# 01_MCU.net
KiCad netlist of a schematic drawn in Altium Designer
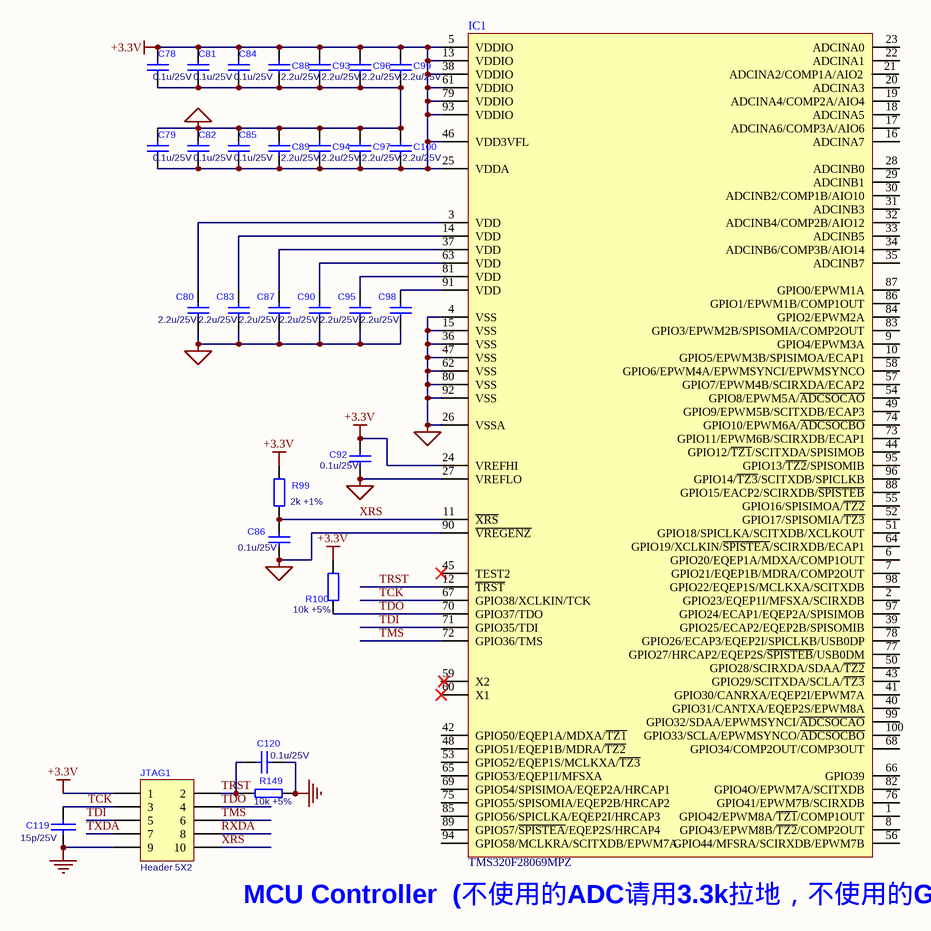
[diagram p0: 01_MCU.SchDoc]

(export (version "E")
  (design (tool "Eeschema 10.0.6"))
  (components
    (comp (ref "C78")
      (value "0.1u/25V")
      (footprint "C0603")
      (description "Capacitor")
      (fields (field (name "PUBLISHER") "Altium Limited"))
      (libsource (lib "*") (part "Cap"))
    )
    (comp (ref "C79")
      (value "0.1u/25V")
      (footprint "R0603")
      (description "Capacitor")
      (fields (field (name "PUBLISHER") "Altium Limited"))
      (libsource (lib "*") (part "Cap"))
    )
    (comp (ref "C80")
      (value "2.2u/25V")
      (footprint "R0603")
      (description "Capacitor")
      (fields (field (name "PUBLISHER") "Altium Limited"))
      (libsource (lib "*") (part "Cap"))
    )
    (comp (ref "C81")
      (value "0.1u/25V")
      (footprint "C0603")
      (description "Capacitor")
      (fields (field (name "PUBLISHER") "Altium Limited"))
      (libsource (lib "*") (part "Cap"))
    )
    (comp (ref "C82")
      (value "0.1u/25V")
      (footprint "R0603")
      (description "Capacitor")
      (fields (field (name "PUBLISHER") "Altium Limited"))
      (libsource (lib "*") (part "Cap"))
    )
    (comp (ref "C83")
      (value "2.2u/25V")
      (footprint "R0603")
      (description "Capacitor")
      (fields (field (name "PUBLISHER") "Altium Limited"))
      (libsource (lib "*") (part "Cap"))
    )
    (comp (ref "C84")
      (value "0.1u/25V")
      (footprint "R0603")
      (description "Capacitor")
      (fields (field (name "PUBLISHER") "Altium Limited"))
      (libsource (lib "*") (part "Cap"))
    )
    (comp (ref "C85")
      (value "0.1u/25V")
      (footprint "R0603")
      (description "Capacitor")
      (fields (field (name "PUBLISHER") "Altium Limited"))
      (libsource (lib "*") (part "Cap"))
    )
    (comp (ref "C86")
      (value "0.1u/25V")
      (footprint "R0603")
      (description "Capacitor")
      (fields (field (name "PUBLISHER") "Altium Limited"))
      (libsource (lib "*") (part "Cap"))
    )
    (comp (ref "C87")
      (value "2.2u/25V")
      (footprint "R0603")
      (description "Capacitor")
      (fields (field (name "PUBLISHER") "Altium Limited"))
      (libsource (lib "*") (part "Cap"))
    )
    (comp (ref "C88")
      (value "2.2u/25V")
      (footprint "R0603")
      (description "Capacitor")
      (fields (field (name "PUBLISHER") "Altium Limited"))
      (libsource (lib "*") (part "Cap"))
    )
    (comp (ref "C89")
      (value "2.2u/25V")
      (footprint "R0603")
      (description "Capacitor")
      (fields (field (name "PUBLISHER") "Altium Limited"))
      (libsource (lib "*") (part "Cap"))
    )
    (comp (ref "C90")
      (value "2.2u/25V")
      (footprint "R0603")
      (description "Capacitor")
      (fields (field (name "PUBLISHER") "Altium Limited"))
      (libsource (lib "*") (part "Cap"))
    )
    (comp (ref "C92")
      (value "0.1u/25V")
      (footprint "R0603")
      (description "Capacitor")
      (fields (field (name "PUBLISHER") "Altium Limited"))
      (libsource (lib "*") (part "Cap"))
    )
    (comp (ref "C93")
      (value "2.2u/25V")
      (footprint "R0603")
      (description "Capacitor")
      (fields (field (name "PUBLISHER") "Altium Limited"))
      (libsource (lib "*") (part "Cap"))
    )
    (comp (ref "C94")
      (value "2.2u/25V")
      (footprint "R0603")
      (description "Capacitor")
      (fields (field (name "PUBLISHER") "Altium Limited"))
      (libsource (lib "*") (part "Cap"))
    )
    (comp (ref "C95")
      (value "2.2u/25V")
      (footprint "R0603")
      (description "Capacitor")
      (fields (field (name "PUBLISHER") "Altium Limited"))
      (libsource (lib "*") (part "Cap"))
    )
    (comp (ref "C96")
      (value "2.2u/25V")
      (footprint "R0603")
      (description "Capacitor")
      (fields (field (name "PUBLISHER") "Altium Limited"))
      (libsource (lib "*") (part "Cap"))
    )
    (comp (ref "C97")
      (value "2.2u/25V")
      (footprint "R0603")
      (description "Capacitor")
      (fields (field (name "PUBLISHER") "Altium Limited"))
      (libsource (lib "*") (part "Cap"))
    )
    (comp (ref "C98")
      (value "2.2u/25V")
      (footprint "R0603")
      (description "Capacitor")
      (fields (field (name "PUBLISHER") "Altium Limited"))
      (libsource (lib "*") (part "Cap"))
    )
    (comp (ref "C99")
      (value "2.2u/25V")
      (footprint "R0603")
      (description "Capacitor")
      (fields (field (name "PUBLISHER") "Altium Limited"))
      (libsource (lib "*") (part "Cap"))
    )
    (comp (ref "C100")
      (value "2.2u/25V")
      (footprint "R0603")
      (description "Capacitor")
      (fields (field (name "PUBLISHER") "Altium Limited"))
      (libsource (lib "*") (part "Cap"))
    )
    (comp (ref "C119")
      (value "15p/25V")
      (footprint "R0603")
      (description "Capacitor")
      (libsource (lib "*") (part "CAP"))
    )
    (comp (ref "C120")
      (value "0.1u/25V")
      (footprint "R0603")
      (description "Capacitor")
      (fields (field (name "PUBLISHER") "Altium Limited"))
      (libsource (lib "*") (part "Cap"))
    )
    (comp (ref "IC1")
      (value "TMS320F28069MPZ")
      (footprint "RX62T")
      (description "TI MCU_TMS320F28069")
      (libsource (lib "*") (part "IC-TMS320F28062"))
    )
    (comp (ref "JTAG1")
      (value "Header 5X2")
      (footprint "PZ-2*5-M-SI")
      (description "Header, 5-Pin, Dual row")
      (fields (field (name "MANUFACTURER") "Generic Components") (field (name "PUBLISHER") "Altium Limited"))
      (libsource (lib "*") (part "Header 5X2"))
    )
    (comp (ref "R99")
      (value "2k +1%")
      (footprint "R0603")
      (description "Resistor")
      (fields (field (name "PUBLISHER") "Altium Limited"))
      (libsource (lib "*") (part "Res2"))
    )
    (comp (ref "R100")
      (value "10k +5%")
      (footprint "R0603")
      (description "Resistor")
      (fields (field (name "PUBLISHER") "Altium Limited"))
      (libsource (lib "*") (part "Res2"))
    )
    (comp (ref "R149") (value "10k +5%") (footprint "R0603") (libsource (lib "*") (part "RES/0603")))
  )
  (nets
    (net (code "1") (name "+3.3V") (class "Default")
      (node (ref "C100") (pin "2") (pinfunction "2_2") (pintype "passive"))
      (node (ref "C78") (pin "1") (pinfunction "1_1") (pintype "passive"))
      (node (ref "C79") (pin "2") (pinfunction "2_2") (pintype "passive"))
      (node (ref "C81") (pin "1") (pinfunction "1_1") (pintype "passive"))
      (node (ref "C82") (pin "2") (pinfunction "2_2") (pintype "passive"))
      (node (ref "C84") (pin "1") (pinfunction "1_1") (pintype "passive"))
      (node (ref "C85") (pin "2") (pinfunction "2_2") (pintype "passive"))
      (node (ref "C88") (pin "1") (pinfunction "1_1") (pintype "passive"))
      (node (ref "C89") (pin "2") (pinfunction "2_2") (pintype "passive"))
      (node (ref "C92") (pin "1") (pinfunction "1_1") (pintype "passive"))
      (node (ref "C93") (pin "1") (pinfunction "1_1") (pintype "passive"))
      (node (ref "C94") (pin "2") (pinfunction "2_2") (pintype "passive"))
      (node (ref "C96") (pin "1") (pinfunction "1_1") (pintype "passive"))
      (node (ref "C97") (pin "2") (pinfunction "2_2") (pintype "passive"))
      (node (ref "C99") (pin "1") (pinfunction "1_1") (pintype "passive"))
      (node (ref "IC1") (pin "13") (pinfunction "VDDIO_13") (pintype "passive"))
      (node (ref "IC1") (pin "24") (pinfunction "VREFHI_24") (pintype "passive"))
      (node (ref "IC1") (pin "25") (pinfunction "VDDA_25") (pintype "passive"))
      (node (ref "IC1") (pin "38") (pinfunction "VDDIO_38") (pintype "passive"))
      (node (ref "IC1") (pin "46") (pinfunction "VDD3VFL_46") (pintype "passive"))
      (node (ref "IC1") (pin "5") (pinfunction "VDDIO_5") (pintype "passive"))
      (node (ref "IC1") (pin "61") (pinfunction "VDDIO_61") (pintype "passive"))
      (node (ref "IC1") (pin "79") (pinfunction "VDDIO_79") (pintype "passive"))
      (node (ref "IC1") (pin "93") (pinfunction "VDDIO_93") (pintype "passive"))
      (node (ref "JTAG1") (pin "1") (pinfunction "1_1") (pintype "passive"))
      (node (ref "R100") (pin "2") (pinfunction "2_2") (pintype "passive"))
      (node (ref "R99") (pin "2") (pinfunction "2_2") (pintype "passive"))
    )
    (net (code "2") (name "/RXDA") (class "Default")
      (node (ref "JTAG1") (pin "8") (pinfunction "8_8") (pintype "passive"))
    )
    (net (code "3") (name "/TCK") (class "Default")
      (node (ref "C119") (pin "1") (pinfunction "1_1") (pintype "passive"))
      (node (ref "IC1") (pin "67") (pinfunction "GPIO38/XCLKIN/TCK_67") (pintype "passive"))
      (node (ref "JTAG1") (pin "3") (pinfunction "3_3") (pintype "passive"))
    )
    (net (code "4") (name "/TDI") (class "Default")
      (node (ref "IC1") (pin "71") (pinfunction "GPIO35/TDI_71") (pintype "passive"))
      (node (ref "JTAG1") (pin "5") (pinfunction "5_5") (pintype "passive"))
    )
    (net (code "5") (name "/TDO") (class "Default")
      (node (ref "IC1") (pin "70") (pinfunction "GPIO37/TDO_70") (pintype "passive"))
      (node (ref "JTAG1") (pin "4") (pinfunction "4_4") (pintype "passive"))
      (node (ref "R100") (pin "1") (pinfunction "1_1") (pintype "passive"))
    )
    (net (code "6") (name "/TMS") (class "Default")
      (node (ref "IC1") (pin "72") (pinfunction "GPIO36/TMS_72") (pintype "passive"))
      (node (ref "JTAG1") (pin "6") (pinfunction "6_6") (pintype "passive"))
    )
    (net (code "7") (name "/TRST") (class "Default")
      (node (ref "C120") (pin "2") (pinfunction "2_2") (pintype "passive"))
      (node (ref "IC1") (pin "12") (pinfunction "~{TRST}_12") (pintype "passive"))
      (node (ref "JTAG1") (pin "2") (pinfunction "2_2") (pintype "passive"))
      (node (ref "R149") (pin "1") (pinfunction "1_1") (pintype "passive"))
    )
    (net (code "8") (name "/TXDA") (class "Default")
      (node (ref "JTAG1") (pin "7") (pinfunction "7_7") (pintype "passive"))
    )
    (net (code "9") (name "/XRS") (class "Default")
      (node (ref "C86") (pin "1") (pinfunction "1_1") (pintype "passive"))
      (node (ref "IC1") (pin "11") (pinfunction "~{XRS}_11") (pintype "passive"))
      (node (ref "JTAG1") (pin "10") (pinfunction "10_10") (pintype "passive"))
      (node (ref "R99") (pin "1") (pinfunction "1_1") (pintype "passive"))
    )
    (net (code "10") (name "GND") (class "Default")
      (node (ref "C100") (pin "1") (pinfunction "1_1") (pintype "passive"))
      (node (ref "C119") (pin "2") (pinfunction "2_2") (pintype "passive"))
      (node (ref "C120") (pin "1") (pinfunction "1_1") (pintype "passive"))
      (node (ref "C78") (pin "2") (pinfunction "2_2") (pintype "passive"))
      (node (ref "C79") (pin "1") (pinfunction "1_1") (pintype "passive"))
      (node (ref "C80") (pin "2") (pinfunction "2_2") (pintype "passive"))
      (node (ref "C81") (pin "2") (pinfunction "2_2") (pintype "passive"))
      (node (ref "C82") (pin "1") (pinfunction "1_1") (pintype "passive"))
      (node (ref "C83") (pin "2") (pinfunction "2_2") (pintype "passive"))
      (node (ref "C84") (pin "2") (pinfunction "2_2") (pintype "passive"))
      (node (ref "C85") (pin "1") (pinfunction "1_1") (pintype "passive"))
      (node (ref "C86") (pin "2") (pinfunction "2_2") (pintype "passive"))
      (node (ref "C87") (pin "2") (pinfunction "2_2") (pintype "passive"))
      (node (ref "C88") (pin "2") (pinfunction "2_2") (pintype "passive"))
      (node (ref "C89") (pin "1") (pinfunction "1_1") (pintype "passive"))
      (node (ref "C90") (pin "2") (pinfunction "2_2") (pintype "passive"))
      (node (ref "C92") (pin "2") (pinfunction "2_2") (pintype "passive"))
      (node (ref "C93") (pin "2") (pinfunction "2_2") (pintype "passive"))
      (node (ref "C94") (pin "1") (pinfunction "1_1") (pintype "passive"))
      (node (ref "C95") (pin "2") (pinfunction "2_2") (pintype "passive"))
      (node (ref "C96") (pin "2") (pinfunction "2_2") (pintype "passive"))
      (node (ref "C97") (pin "1") (pinfunction "1_1") (pintype "passive"))
      (node (ref "C98") (pin "2") (pinfunction "2_2") (pintype "passive"))
      (node (ref "C99") (pin "2") (pinfunction "2_2") (pintype "passive"))
      (node (ref "IC1") (pin "15") (pinfunction "VSS_15") (pintype "passive"))
      (node (ref "IC1") (pin "26") (pinfunction "VSSA_26") (pintype "passive"))
      (node (ref "IC1") (pin "27") (pinfunction "VREFLO_27") (pintype "passive"))
      (node (ref "IC1") (pin "36") (pinfunction "VSS_36") (pintype "passive"))
      (node (ref "IC1") (pin "4") (pinfunction "VSS_4") (pintype "passive"))
      (node (ref "IC1") (pin "47") (pinfunction "VSS_47") (pintype "passive"))
      (node (ref "IC1") (pin "62") (pinfunction "VSS_62") (pintype "passive"))
      (node (ref "IC1") (pin "80") (pinfunction "VSS_80") (pintype "passive"))
      (node (ref "IC1") (pin "90") (pinfunction "~{VREGENZ}_90") (pintype "passive"))
      (node (ref "IC1") (pin "92") (pinfunction "VSS_92") (pintype "passive"))
      (node (ref "JTAG1") (pin "9") (pinfunction "9_9") (pintype "passive"))
      (node (ref "R149") (pin "2") (pinfunction "2_2") (pintype "passive"))
    )
    (net (code "11") (name "Net-(C80-Pad1)") (class "Default")
      (node (ref "C80") (pin "1") (pinfunction "1_1") (pintype "passive"))
      (node (ref "IC1") (pin "3") (pinfunction "VDD_3") (pintype "passive"))
    )
    (net (code "12") (name "Net-(C83-Pad1)") (class "Default")
      (node (ref "C83") (pin "1") (pinfunction "1_1") (pintype "passive"))
      (node (ref "IC1") (pin "14") (pinfunction "VDD_14") (pintype "passive"))
    )
    (net (code "13") (name "Net-(C87-Pad1)") (class "Default")
      (node (ref "C87") (pin "1") (pinfunction "1_1") (pintype "passive"))
      (node (ref "IC1") (pin "37") (pinfunction "VDD_37") (pintype "passive"))
    )
    (net (code "14") (name "Net-(C90-Pad1)") (class "Default")
      (node (ref "C90") (pin "1") (pinfunction "1_1") (pintype "passive"))
      (node (ref "IC1") (pin "63") (pinfunction "VDD_63") (pintype "passive"))
    )
    (net (code "15") (name "Net-(C95-Pad1)") (class "Default")
      (node (ref "C95") (pin "1") (pinfunction "1_1") (pintype "passive"))
      (node (ref "IC1") (pin "81") (pinfunction "VDD_81") (pintype "passive"))
    )
    (net (code "16") (name "Net-(C98-Pad1)") (class "Default")
      (node (ref "C98") (pin "1") (pinfunction "1_1") (pintype "passive"))
      (node (ref "IC1") (pin "91") (pinfunction "VDD_91") (pintype "passive"))
    )
    (net (code "17") (name "unconnected-(IC1-ADCINA0-Pad23)") (class "Default")
      (node (ref "IC1") (pin "23") (pinfunction "ADCINA0_23") (pintype "passive"))
    )
    (net (code "18") (name "unconnected-(IC1-ADCINA1-Pad22)") (class "Default")
      (node (ref "IC1") (pin "22") (pinfunction "ADCINA1_22") (pintype "passive"))
    )
    (net (code "19") (name "unconnected-(IC1-ADCINA2{slash}COMP1A{slash}AIO2-Pad21)") (class "Default")
      (node (ref "IC1") (pin "21") (pinfunction "ADCINA2/COMP1A/AIO2_21") (pintype "passive"))
    )
    (net (code "20") (name "unconnected-(IC1-ADCINA3-Pad20)") (class "Default")
      (node (ref "IC1") (pin "20") (pinfunction "ADCINA3_20") (pintype "passive"))
    )
    (net (code "21") (name "unconnected-(IC1-ADCINA4{slash}COMP2A{slash}AIO4-Pad19)") (class "Default")
      (node (ref "IC1") (pin "19") (pinfunction "ADCINA4/COMP2A/AIO4_19") (pintype "passive"))
    )
    (net (code "22") (name "unconnected-(IC1-ADCINA5-Pad18)") (class "Default")
      (node (ref "IC1") (pin "18") (pinfunction "ADCINA5_18") (pintype "passive"))
    )
    (net (code "23") (name "unconnected-(IC1-ADCINA6{slash}COMP3A{slash}AIO6-Pad17)") (class "Default")
      (node (ref "IC1") (pin "17") (pinfunction "ADCINA6/COMP3A/AIO6_17") (pintype "passive"))
    )
    (net (code "24") (name "unconnected-(IC1-ADCINA7-Pad16)") (class "Default")
      (node (ref "IC1") (pin "16") (pinfunction "ADCINA7_16") (pintype "passive"))
    )
    (net (code "25") (name "unconnected-(IC1-ADCINB0-Pad28)") (class "Default")
      (node (ref "IC1") (pin "28") (pinfunction "ADCINB0_28") (pintype "passive"))
    )
    (net (code "26") (name "unconnected-(IC1-ADCINB1-Pad29)") (class "Default")
      (node (ref "IC1") (pin "29") (pinfunction "ADCINB1_29") (pintype "passive"))
    )
    (net (code "27") (name "unconnected-(IC1-ADCINB2{slash}COMP1B{slash}AIO10-Pad30)") (class "Default")
      (node (ref "IC1") (pin "30") (pinfunction "ADCINB2/COMP1B/AIO10_30") (pintype "passive"))
    )
    (net (code "28") (name "unconnected-(IC1-ADCINB3-Pad31)") (class "Default")
      (node (ref "IC1") (pin "31") (pinfunction "ADCINB3_31") (pintype "passive"))
    )
    (net (code "29") (name "unconnected-(IC1-ADCINB4{slash}COMP2B{slash}AIO12-Pad32)") (class "Default")
      (node (ref "IC1") (pin "32") (pinfunction "ADCINB4/COMP2B/AIO12_32") (pintype "passive"))
    )
    (net (code "30") (name "unconnected-(IC1-ADCINB5-Pad33)") (class "Default")
      (node (ref "IC1") (pin "33") (pinfunction "ADCINB5_33") (pintype "passive"))
    )
    (net (code "31") (name "unconnected-(IC1-ADCINB6{slash}COMP3B{slash}AIO14-Pad34)") (class "Default")
      (node (ref "IC1") (pin "34") (pinfunction "ADCINB6/COMP3B/AIO14_34") (pintype "passive"))
    )
    (net (code "32") (name "unconnected-(IC1-ADCINB7-Pad35)") (class "Default")
      (node (ref "IC1") (pin "35") (pinfunction "ADCINB7_35") (pintype "passive"))
    )
    (net (code "33") (name "unconnected-(IC1-GPIO0{slash}EPWM1A-Pad87)") (class "Default")
      (node (ref "IC1") (pin "87") (pinfunction "GPIO0/EPWM1A_87") (pintype "passive"))
    )
    (net (code "34") (name "unconnected-(IC1-GPIO1{slash}EPWM1B{slash}COMP1OUT-Pad86)") (class "Default")
      (node (ref "IC1") (pin "86") (pinfunction "GPIO1/EPWM1B/COMP1OUT_86") (pintype "passive"))
    )
    (net (code "35") (name "unconnected-(IC1-GPIO2{slash}EPWM2A-Pad84)") (class "Default")
      (node (ref "IC1") (pin "84") (pinfunction "GPIO2/EPWM2A_84") (pintype "passive"))
    )
    (net (code "36") (name "unconnected-(IC1-GPIO3{slash}EPWM2B{slash}SPISOMIA{slash}COMP2OUT-Pad83)") (class "Default")
      (node (ref "IC1") (pin "83") (pinfunction "GPIO3/EPWM2B/SPISOMIA/COMP2OUT_83") (pintype "passive"))
    )
    (net (code "37") (name "unconnected-(IC1-GPIO4O{slash}EPWM7A{slash}SCITXDB-Pad82)") (class "Default")
      (node (ref "IC1") (pin "82") (pinfunction "GPIO4O/EPWM7A/SCITXDB_82") (pintype "passive"))
    )
    (net (code "38") (name "unconnected-(IC1-GPIO4{slash}EPWM3A-Pad9)") (class "Default")
      (node (ref "IC1") (pin "9") (pinfunction "GPIO4/EPWM3A_9") (pintype "passive"))
    )
    (net (code "39") (name "unconnected-(IC1-GPIO5{slash}EPWM3B{slash}SPISIMOA{slash}ECAP1-Pad10)") (class "Default")
      (node (ref "IC1") (pin "10") (pinfunction "GPIO5/EPWM3B/SPISIMOA/ECAP1_10") (pintype "passive"))
    )
    (net (code "40") (name "unconnected-(IC1-GPIO6{slash}EPWM4A{slash}EPWMSYNCI{slash}EPWMSYNCO-Pad58)") (class "Default")
      (node (ref "IC1") (pin "58") (pinfunction "GPIO6/EPWM4A/EPWMSYNCI/EPWMSYNCO_58") (pintype "passive"))
    )
    (net (code "41") (name "unconnected-(IC1-GPIO7{slash}EPWM4B{slash}SCIRXDA{slash}ECAP2-Pad57)") (class "Default")
      (node (ref "IC1") (pin "57") (pinfunction "GPIO7/EPWM4B/SCIRXDA/ECAP2_57") (pintype "passive"))
    )
    (net (code "42") (name "unconnected-(IC1-GPIO8{slash}EPWM5A{slash}~{ADCSOCAO}-Pad54)") (class "Default")
      (node (ref "IC1") (pin "54") (pinfunction "GPIO8/EPWM5A/~{ADCSOCAO}_54") (pintype "passive"))
    )
    (net (code "43") (name "unconnected-(IC1-GPIO9{slash}EPWM5B{slash}SCITXDB{slash}ECAP3-Pad49)") (class "Default")
      (node (ref "IC1") (pin "49") (pinfunction "GPIO9/EPWM5B/SCITXDB/ECAP3_49") (pintype "passive"))
    )
    (net (code "44") (name "unconnected-(IC1-GPIO10{slash}EPWM6A{slash}~{ADCSOCBO}-Pad74)") (class "Default")
      (node (ref "IC1") (pin "74") (pinfunction "GPIO10/EPWM6A/~{ADCSOCBO}_74") (pintype "passive"))
    )
    (net (code "45") (name "unconnected-(IC1-GPIO11{slash}EPWM6B{slash}SCIRXDB{slash}ECAP1-Pad73)") (class "Default")
      (node (ref "IC1") (pin "73") (pinfunction "GPIO11/EPWM6B/SCIRXDB/ECAP1_73") (pintype "passive"))
    )
    (net (code "46") (name "unconnected-(IC1-GPIO12{slash}~{TZ1}{slash}SCITXDA{slash}SPISIMOB-Pad44)") (class "Default")
      (node (ref "IC1") (pin "44") (pinfunction "GPIO12/~{TZ1}/SCITXDA/SPISIMOB_44") (pintype "passive"))
    )
    (net (code "47") (name "unconnected-(IC1-GPIO13{slash}~{TZ2}{slash}SPISOMIB-Pad95)") (class "Default")
      (node (ref "IC1") (pin "95") (pinfunction "GPIO13/~{TZ2}/SPISOMIB_95") (pintype "passive"))
    )
    (net (code "48") (name "unconnected-(IC1-GPIO14{slash}~{TZ3}{slash}SCITXDB{slash}SPICLKB-Pad96)") (class "Default")
      (node (ref "IC1") (pin "96") (pinfunction "GPIO14/~{TZ3}/SCITXDB/SPICLKB_96") (pintype "passive"))
    )
    (net (code "49") (name "unconnected-(IC1-GPIO15{slash}EACP2{slash}SCIRXDB{slash}~{SPISTEB}-Pad88)") (class "Default")
      (node (ref "IC1") (pin "88") (pinfunction "GPIO15/EACP2/SCIRXDB/~{SPISTEB}_88") (pintype "passive"))
    )
    (net (code "50") (name "unconnected-(IC1-GPIO16{slash}SPISIMOA{slash}~{TZ2}-Pad55)") (class "Default")
      (node (ref "IC1") (pin "55") (pinfunction "GPIO16/SPISIMOA/~{TZ2}_55") (pintype "passive"))
    )
    (net (code "51") (name "unconnected-(IC1-GPIO17{slash}SPISOMIA{slash}~{TZ3}-Pad52)") (class "Default")
      (node (ref "IC1") (pin "52") (pinfunction "GPIO17/SPISOMIA/~{TZ3}_52") (pintype "passive"))
    )
    (net (code "52") (name "unconnected-(IC1-GPIO18{slash}SPICLKA{slash}SCITXDB{slash}XCLKOUT-Pad51)") (class "Default")
      (node (ref "IC1") (pin "51") (pinfunction "GPIO18/SPICLKA/SCITXDB/XCLKOUT_51") (pintype "passive"))
    )
    (net (code "53") (name "unconnected-(IC1-GPIO19{slash}XCLKIN{slash}~{SPISTEA}{slash}SCIRXDB{slash}ECAP1-Pad64)") (class "Default")
      (node (ref "IC1") (pin "64") (pinfunction "GPIO19/XCLKIN/~{SPISTEA}/SCIRXDB/ECAP1_64") (pintype "passive"))
    )
    (net (code "54") (name "unconnected-(IC1-GPIO20{slash}EQEP1A{slash}MDXA{slash}COMP1OUT-Pad6)") (class "Default")
      (node (ref "IC1") (pin "6") (pinfunction "GPIO20/EQEP1A/MDXA/COMP1OUT_6") (pintype "passive"))
    )
    (net (code "55") (name "unconnected-(IC1-GPIO21{slash}EQEP1B{slash}MDRA{slash}COMP2OUT-Pad7)") (class "Default")
      (node (ref "IC1") (pin "7") (pinfunction "GPIO21/EQEP1B/MDRA/COMP2OUT_7") (pintype "passive"))
    )
    (net (code "56") (name "unconnected-(IC1-GPIO22{slash}EQEP1S{slash}MCLKXA{slash}SCITXDB-Pad98)") (class "Default")
      (node (ref "IC1") (pin "98") (pinfunction "GPIO22/EQEP1S/MCLKXA/SCITXDB_98") (pintype "passive"))
    )
    (net (code "57") (name "unconnected-(IC1-GPIO23{slash}EQEP1I{slash}MFSXA{slash}SCIRXDB-Pad2)") (class "Default")
      (node (ref "IC1") (pin "2") (pinfunction "GPIO23/EQEP1I/MFSXA/SCIRXDB_2") (pintype "passive"))
    )
    (net (code "58") (name "unconnected-(IC1-GPIO24{slash}ECAP1{slash}EQEP2A{slash}SPISIMOB-Pad97)") (class "Default")
      (node (ref "IC1") (pin "97") (pinfunction "GPIO24/ECAP1/EQEP2A/SPISIMOB_97") (pintype "passive"))
    )
    (net (code "59") (name "unconnected-(IC1-GPIO25{slash}ECAP2{slash}EQEP2B{slash}SPISOMIB-Pad39)") (class "Default")
      (node (ref "IC1") (pin "39") (pinfunction "GPIO25/ECAP2/EQEP2B/SPISOMIB_39") (pintype "passive"))
    )
    (net (code "60") (name "unconnected-(IC1-GPIO26{slash}ECAP3{slash}EQEP2I{slash}SPICLKB{slash}USB0DP-Pad78)") (class "Default")
      (node (ref "IC1") (pin "78") (pinfunction "GPIO26/ECAP3/EQEP2I/SPICLKB/USB0DP_78") (pintype "passive"))
    )
    (net (code "61") (name "unconnected-(IC1-GPIO27{slash}HRCAP2{slash}EQEP2S{slash}~{SPISTEB}{slash}USB0DM-Pad77)") (class "Default")
      (node (ref "IC1") (pin "77") (pinfunction "GPIO27/HRCAP2/EQEP2S/~{SPISTEB}/USB0DM_77") (pintype "passive"))
    )
    (net (code "62") (name "unconnected-(IC1-GPIO28{slash}SCIRXDA{slash}SDAA{slash}~{TZ2}-Pad50)") (class "Default")
      (node (ref "IC1") (pin "50") (pinfunction "GPIO28/SCIRXDA/SDAA/~{TZ2}_50") (pintype "passive"))
    )
    (net (code "63") (name "unconnected-(IC1-GPIO29{slash}SCITXDA{slash}SCLA{slash}~{TZ3}-Pad43)") (class "Default")
      (node (ref "IC1") (pin "43") (pinfunction "GPIO29/SCITXDA/SCLA/~{TZ3}_43") (pintype "passive"))
    )
    (net (code "64") (name "unconnected-(IC1-GPIO30{slash}CANRXA{slash}EQEP2I{slash}EPWM7A-Pad41)") (class "Default")
      (node (ref "IC1") (pin "41") (pinfunction "GPIO30/CANRXA/EQEP2I/EPWM7A_41") (pintype "passive"))
    )
    (net (code "65") (name "unconnected-(IC1-GPIO31{slash}CANTXA{slash}EQEP2S{slash}EPWM8A-Pad40)") (class "Default")
      (node (ref "IC1") (pin "40") (pinfunction "GPIO31/CANTXA/EQEP2S/EPWM8A_40") (pintype "passive"))
    )
    (net (code "66") (name "unconnected-(IC1-GPIO32{slash}SDAA{slash}EPWMSYNCI{slash}~{ADCSOCAO}-Pad99)") (class "Default")
      (node (ref "IC1") (pin "99") (pinfunction "GPIO32/SDAA/EPWMSYNCI/~{ADCSOCAO}_99") (pintype "passive"))
    )
    (net (code "67") (name "unconnected-(IC1-GPIO33{slash}SCLA{slash}EPWMSYNCO{slash}~{ADCSOCBO}-Pad100)") (class "Default")
      (node (ref "IC1") (pin "100") (pinfunction "GPIO33/SCLA/EPWMSYNCO/~{ADCSOCBO}_100") (pintype "passive"))
    )
    (net (code "68") (name "unconnected-(IC1-GPIO34{slash}COMP2OUT{slash}COMP3OUT-Pad68)") (class "Default")
      (node (ref "IC1") (pin "68") (pinfunction "GPIO34/COMP2OUT/COMP3OUT_68") (pintype "passive"))
    )
    (net (code "69") (name "unconnected-(IC1-GPIO39-Pad66)") (class "Default")
      (node (ref "IC1") (pin "66") (pinfunction "GPIO39_66") (pintype "passive"))
    )
    (net (code "70") (name "unconnected-(IC1-GPIO41{slash}EPWM7B{slash}SCIRXDB-Pad76)") (class "Default")
      (node (ref "IC1") (pin "76") (pinfunction "GPIO41/EPWM7B/SCIRXDB_76") (pintype "passive"))
    )
    (net (code "71") (name "unconnected-(IC1-GPIO42{slash}EPWM8A{slash}~{TZ1}{slash}COMP1OUT-Pad1)") (class "Default")
      (node (ref "IC1") (pin "1") (pinfunction "GPIO42/EPWM8A/~{TZ1}/COMP1OUT_1") (pintype "passive"))
    )
    (net (code "72") (name "unconnected-(IC1-GPIO43{slash}EPWM8B{slash}~{TZ2}{slash}COMP2OUT-Pad8)") (class "Default")
      (node (ref "IC1") (pin "8") (pinfunction "GPIO43/EPWM8B/~{TZ2}/COMP2OUT_8") (pintype "passive"))
    )
    (net (code "73") (name "unconnected-(IC1-GPIO44{slash}MFSRA{slash}SCIRXDB{slash}EPWM7B-Pad56)") (class "Default")
      (node (ref "IC1") (pin "56") (pinfunction "GPIO44/MFSRA/SCIRXDB/EPWM7B_56") (pintype "passive"))
    )
    (net (code "74") (name "unconnected-(IC1-GPIO50{slash}EQEP1A{slash}MDXA{slash}~{TZ1}-Pad42)") (class "Default")
      (node (ref "IC1") (pin "42") (pinfunction "GPIO50/EQEP1A/MDXA/~{TZ1}_42") (pintype "passive"))
    )
    (net (code "75") (name "unconnected-(IC1-GPIO51{slash}EQEP1B{slash}MDRA{slash}~{TZ2}-Pad48)") (class "Default")
      (node (ref "IC1") (pin "48") (pinfunction "GPIO51/EQEP1B/MDRA/~{TZ2}_48") (pintype "passive"))
    )
    (net (code "76") (name "unconnected-(IC1-GPIO52{slash}EQEP1S{slash}MCLKXA{slash}~{TZ3}-Pad53)") (class "Default")
      (node (ref "IC1") (pin "53") (pinfunction "GPIO52/EQEP1S/MCLKXA/~{TZ3}_53") (pintype "passive"))
    )
    (net (code "77") (name "unconnected-(IC1-GPIO53{slash}EQEP1I{slash}MFSXA-Pad65)") (class "Default")
      (node (ref "IC1") (pin "65") (pinfunction "GPIO53/EQEP1I/MFSXA_65") (pintype "passive"))
    )
    (net (code "78") (name "unconnected-(IC1-GPIO54{slash}SPISIMOA{slash}EQEP2A{slash}HRCAP1-Pad69)") (class "Default")
      (node (ref "IC1") (pin "69") (pinfunction "GPIO54/SPISIMOA/EQEP2A/HRCAP1_69") (pintype "passive"))
    )
    (net (code "79") (name "unconnected-(IC1-GPIO55{slash}SPISOMIA{slash}EQEP2B{slash}HRCAP2-Pad75)") (class "Default")
      (node (ref "IC1") (pin "75") (pinfunction "GPIO55/SPISOMIA/EQEP2B/HRCAP2_75") (pintype "passive"))
    )
    (net (code "80") (name "unconnected-(IC1-GPIO56{slash}SPICLKA{slash}EQEP2I{slash}HRCAP3-Pad85)") (class "Default")
      (node (ref "IC1") (pin "85") (pinfunction "GPIO56/SPICLKA/EQEP2I/HRCAP3_85") (pintype "passive"))
    )
    (net (code "81") (name "unconnected-(IC1-GPIO57{slash}~{SPISTEA}{slash}EQEP2S{slash}HRCAP4-Pad89)") (class "Default")
      (node (ref "IC1") (pin "89") (pinfunction "GPIO57/~{SPISTEA}/EQEP2S/HRCAP4_89") (pintype "passive"))
    )
    (net (code "82") (name "unconnected-(IC1-GPIO58{slash}MCLKRA{slash}SCITXDB{slash}EPWM7A-Pad94)") (class "Default")
      (node (ref "IC1") (pin "94") (pinfunction "GPIO58/MCLKRA/SCITXDB/EPWM7A_94") (pintype "passive"))
    )
    (net (code "83") (name "unconnected-(IC1-TEST2-Pad45)") (class "Default")
      (node (ref "IC1") (pin "45") (pinfunction "TEST2_45") (pintype "passive+no_connect"))
    )
    (net (code "84") (name "unconnected-(IC1-X1-Pad60)") (class "Default")
      (node (ref "IC1") (pin "60") (pinfunction "X1_60") (pintype "passive+no_connect"))
    )
    (net (code "85") (name "unconnected-(IC1-X2-Pad59)") (class "Default")
      (node (ref "IC1") (pin "59") (pinfunction "X2_59") (pintype "passive"))
    )
  )
)
